# ECE445_Interrogator_Schematic.net
KiCad netlist of a schematic drawn in EAGLE
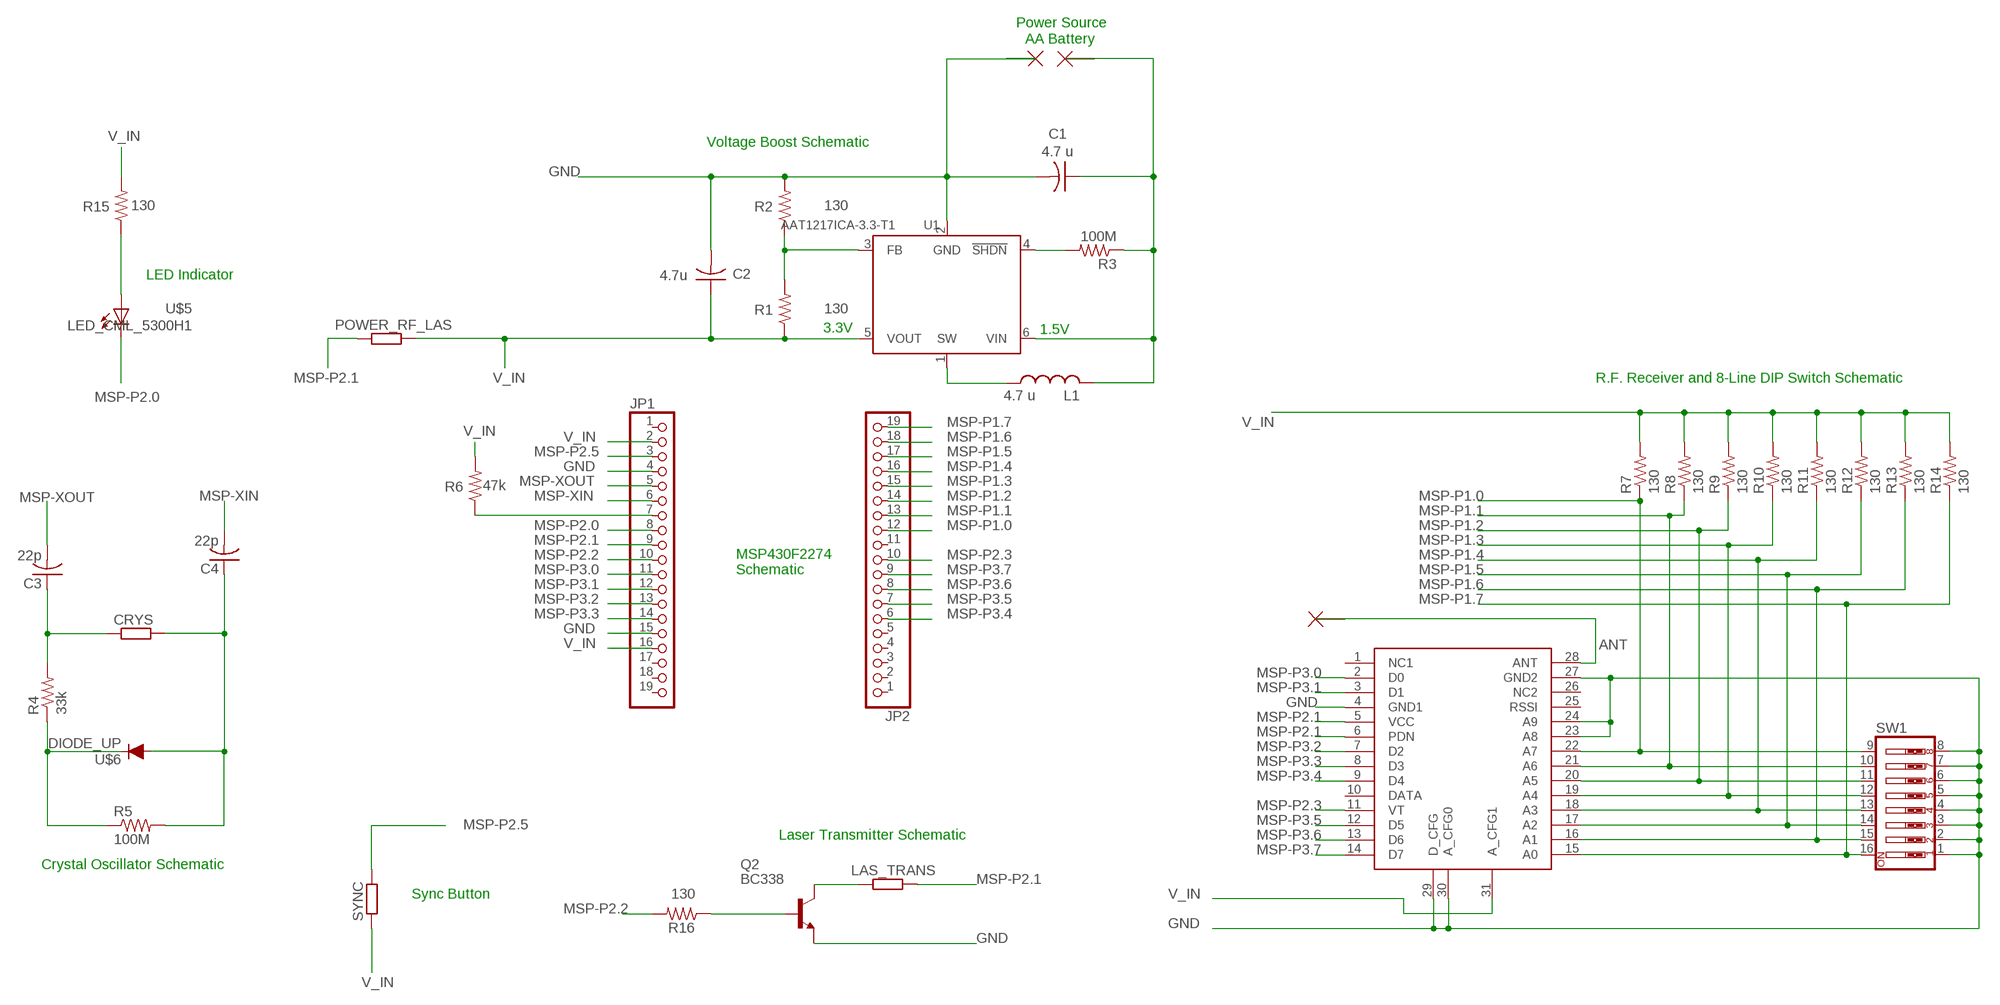
[diagram p0: schematic, sheet 1]

(export (version "E")
  (design (tool "Eeschema 10.0.6"))
  (components
    (comp (ref "C1")
      (value "4.7 u")
      (footprint "eagle-import:C025-024X044")
      (libsource (lib "eagle-import") (part "C-US025-024X044"))
    )
    (comp (ref "C2")
      (value "4.7u")
      (footprint "eagle-import:C025-024X044")
      (libsource (lib "eagle-import") (part "C-US025-024X044"))
    )
    (comp (ref "C3")
      (value "22p")
      (footprint "eagle-import:C025-024X044")
      (libsource (lib "eagle-import") (part "C-US025-024X044"))
    )
    (comp (ref "C4")
      (value "22p")
      (footprint "eagle-import:C025-024X044")
      (libsource (lib "eagle-import") (part "C-US025-024X044"))
    )
    (comp (ref "CRYS")
      (value "R-EU_0204/5")
      (footprint "eagle-import:0204_5")
      (libsource (lib "eagle-import") (part "R-EU_0204/5"))
    )
    (comp (ref "JP1")
      (value "PINHD-1X19")
      (footprint "eagle-import:1X19")
      (libsource (lib "eagle-import") (part "PINHD-1X19"))
    )
    (comp (ref "JP2")
      (value "PINHD-1X19")
      (footprint "eagle-import:1X19")
      (libsource (lib "eagle-import") (part "PINHD-1X19"))
    )
    (comp (ref "L1")
      (value "4.7 u")
      (footprint "eagle-import:0204_5")
      (libsource (lib "eagle-import") (part "L-US0204/5"))
    )
    (comp (ref "LAS_TRANS")
      (value "R-EU_0204/5")
      (footprint "eagle-import:0204_5")
      (libsource (lib "eagle-import") (part "R-EU_0204/5"))
    )
    (comp (ref "POWER_RF_LAS")
      (value "R-EU_0204/5")
      (footprint "eagle-import:0204_5")
      (libsource (lib "eagle-import") (part "R-EU_0204/5"))
    )
    (comp (ref "Q2")
      (value "BC338")
      (footprint "eagle-import:TO92-EBC")
      (libsource (lib "eagle-import") (part "BC338"))
    )
    (comp (ref "R1")
      (value "130")
      (footprint "eagle-import:0204_5")
      (libsource (lib "eagle-import") (part "R-US_0204/5"))
    )
    (comp (ref "R2")
      (value "130")
      (footprint "eagle-import:0204_5")
      (libsource (lib "eagle-import") (part "R-US_0204/5"))
    )
    (comp (ref "R3")
      (value "100M")
      (footprint "eagle-import:0204V")
      (libsource (lib "eagle-import") (part "R-US_0204/2V"))
    )
    (comp (ref "R4")
      (value "33k")
      (footprint "eagle-import:0204V")
      (libsource (lib "eagle-import") (part "R-US_0204/2V"))
    )
    (comp (ref "R5")
      (value "100M")
      (footprint "eagle-import:0204V")
      (libsource (lib "eagle-import") (part "R-US_0204/2V"))
    )
    (comp (ref "R6")
      (value "47k")
      (footprint "eagle-import:0204_5")
      (libsource (lib "eagle-import") (part "R-US_0204/5"))
    )
    (comp (ref "R7")
      (value "130")
      (footprint "eagle-import:0204_5")
      (libsource (lib "eagle-import") (part "R-US_0204/5"))
    )
    (comp (ref "R8")
      (value "130")
      (footprint "eagle-import:0204_5")
      (libsource (lib "eagle-import") (part "R-US_0204/5"))
    )
    (comp (ref "R9")
      (value "130")
      (footprint "eagle-import:0204_5")
      (libsource (lib "eagle-import") (part "R-US_0204/5"))
    )
    (comp (ref "R10")
      (value "130")
      (footprint "eagle-import:0204_5")
      (libsource (lib "eagle-import") (part "R-US_0204/5"))
    )
    (comp (ref "R11")
      (value "130")
      (footprint "eagle-import:0204_5")
      (libsource (lib "eagle-import") (part "R-US_0204/5"))
    )
    (comp (ref "R12")
      (value "130")
      (footprint "eagle-import:0204_5")
      (libsource (lib "eagle-import") (part "R-US_0204/5"))
    )
    (comp (ref "R13")
      (value "130")
      (footprint "eagle-import:0204_5")
      (libsource (lib "eagle-import") (part "R-US_0204/5"))
    )
    (comp (ref "R14")
      (value "130")
      (footprint "eagle-import:0204_5")
      (libsource (lib "eagle-import") (part "R-US_0204/5"))
    )
    (comp (ref "R15")
      (value "130")
      (footprint "eagle-import:0204_5")
      (libsource (lib "eagle-import") (part "R-US_0204/5"))
    )
    (comp (ref "R16")
      (value "130")
      (footprint "eagle-import:0204_5")
      (libsource (lib "eagle-import") (part "R-US_0204/5"))
    )
    (comp (ref "SW1")
      (value "SW_DIP-8")
      (footprint "eagle-import:EDG-08")
      (libsource (lib "eagle-import") (part "SW_DIP-8"))
    )
    (comp (ref "SYNC")
      (value "R-EU_0204/5")
      (footprint "eagle-import:0204_5")
      (libsource (lib "eagle-import") (part "R-EU_0204/5"))
    )
    (comp (ref "U$1")
      (value "KH3-RXM-LINX-315")
      (footprint "eagle-import:KH3-RXM-LINX-315")
      (libsource (lib "eagle-import") (part "KH3-RXM-LINX-315"))
    )
    (comp (ref "U$2")
      (value "NO_CONNECT")
      (footprint "eagle-import:NO_CONNECT")
      (libsource (lib "eagle-import") (part "NO_CONNECT"))
    )
    (comp (ref "U$3")
      (value "NO_CONNECT")
      (footprint "eagle-import:NO_CONNECT")
      (libsource (lib "eagle-import") (part "NO_CONNECT"))
    )
    (comp (ref "U$4")
      (value "NO_CONNECT")
      (footprint "eagle-import:NO_CONNECT")
      (libsource (lib "eagle-import") (part "NO_CONNECT"))
    )
    (comp (ref "U$5")
      (value "LED_CML_5300H1")
      (footprint "eagle-import:LED_CML_5300H1")
      (libsource (lib "eagle-import") (part "LED_CML_5300H1"))
    )
    (comp (ref "U$6")
      (value "DIODE_UP")
      (footprint "eagle-import:DIODEUP")
      (libsource (lib "eagle-import") (part "DIODE_UP"))
    )
    (comp (ref "U1")
      (value "AAT1217ICA-3.3-T1")
      (footprint "eagle-import:TSOT-23-6")
      (libsource (lib "eagle-import") (part "AAT1217ICA-3.3-T1"))
    )
  )
  (nets
    (net (code "1") (name "/ANT") (class "Default")
      (node (ref "U$1") (pin "28") (pinfunction "ANT_28") (pintype "bidirectional"))
      (node (ref "U$4") (pin "P$1") (pinfunction "NC_P$1") (pintype "bidirectional"))
    )
    (net (code "2") (name "/GND") (class "Default")
      (node (ref "C1") (pin "2") (pinfunction "2_2") (pintype "passive"))
      (node (ref "C2") (pin "2") (pinfunction "2_2") (pintype "passive"))
      (node (ref "JP1") (pin "15") (pinfunction "15_15") (pintype "passive"))
      (node (ref "JP1") (pin "4") (pinfunction "4_4") (pintype "passive"))
      (node (ref "Q2") (pin "E") (pinfunction "E_E") (pintype "passive"))
      (node (ref "R2") (pin "2") (pinfunction "2_2") (pintype "passive"))
      (node (ref "SW1") (pin "1") (pinfunction "1_1") (pintype "passive"))
      (node (ref "SW1") (pin "2") (pinfunction "2_2") (pintype "passive"))
      (node (ref "SW1") (pin "3") (pinfunction "3_3") (pintype "passive"))
      (node (ref "SW1") (pin "4") (pinfunction "4_4") (pintype "passive"))
      (node (ref "SW1") (pin "5") (pinfunction "5_5") (pintype "passive"))
      (node (ref "SW1") (pin "6") (pinfunction "6_6") (pintype "passive"))
      (node (ref "SW1") (pin "7") (pinfunction "7_7") (pintype "passive"))
      (node (ref "SW1") (pin "8") (pinfunction "8_8") (pintype "passive"))
      (node (ref "U$1") (pin "23") (pinfunction "A8_23") (pintype "bidirectional"))
      (node (ref "U$1") (pin "24") (pinfunction "A9_24") (pintype "bidirectional"))
      (node (ref "U$1") (pin "27") (pinfunction "GND2_27") (pintype "bidirectional"))
      (node (ref "U$1") (pin "29") (pinfunction "D_CFG_29") (pintype "bidirectional"))
      (node (ref "U$1") (pin "30") (pinfunction "A_CFG0_30") (pintype "bidirectional"))
      (node (ref "U$1") (pin "4") (pinfunction "GND1_4") (pintype "bidirectional"))
      (node (ref "U$2") (pin "P$1") (pinfunction "NC_P$1") (pintype "bidirectional"))
      (node (ref "U1") (pin "2") (pinfunction "GND_2") (pintype "bidirectional"))
    )
    (net (code "3") (name "/MSP-P1.0") (class "Default")
      (node (ref "JP2") (pin "12") (pinfunction "12_12") (pintype "passive"))
      (node (ref "R7") (pin "1") (pinfunction "1_1") (pintype "passive"))
      (node (ref "SW1") (pin "9") (pinfunction "9_9") (pintype "passive"))
      (node (ref "U$1") (pin "22") (pinfunction "A7_22") (pintype "bidirectional"))
    )
    (net (code "4") (name "/MSP-P1.1") (class "Default")
      (node (ref "JP2") (pin "13") (pinfunction "13_13") (pintype "passive"))
      (node (ref "R8") (pin "1") (pinfunction "1_1") (pintype "passive"))
      (node (ref "SW1") (pin "10") (pinfunction "10_10") (pintype "passive"))
      (node (ref "U$1") (pin "21") (pinfunction "A6_21") (pintype "bidirectional"))
    )
    (net (code "5") (name "/MSP-P1.2") (class "Default")
      (node (ref "JP2") (pin "14") (pinfunction "14_14") (pintype "passive"))
      (node (ref "R9") (pin "1") (pinfunction "1_1") (pintype "passive"))
      (node (ref "SW1") (pin "11") (pinfunction "11_11") (pintype "passive"))
      (node (ref "U$1") (pin "20") (pinfunction "A5_20") (pintype "bidirectional"))
    )
    (net (code "6") (name "/MSP-P1.3") (class "Default")
      (node (ref "JP2") (pin "15") (pinfunction "15_15") (pintype "passive"))
      (node (ref "R10") (pin "1") (pinfunction "1_1") (pintype "passive"))
      (node (ref "SW1") (pin "12") (pinfunction "12_12") (pintype "passive"))
      (node (ref "U$1") (pin "19") (pinfunction "A4_19") (pintype "bidirectional"))
    )
    (net (code "7") (name "/MSP-P1.4") (class "Default")
      (node (ref "JP2") (pin "16") (pinfunction "16_16") (pintype "passive"))
      (node (ref "R11") (pin "1") (pinfunction "1_1") (pintype "passive"))
      (node (ref "SW1") (pin "13") (pinfunction "13_13") (pintype "passive"))
      (node (ref "U$1") (pin "18") (pinfunction "A3_18") (pintype "bidirectional"))
    )
    (net (code "8") (name "/MSP-P1.5") (class "Default")
      (node (ref "JP2") (pin "17") (pinfunction "17_17") (pintype "passive"))
      (node (ref "R12") (pin "1") (pinfunction "1_1") (pintype "passive"))
      (node (ref "SW1") (pin "14") (pinfunction "14_14") (pintype "passive"))
      (node (ref "U$1") (pin "17") (pinfunction "A2_17") (pintype "bidirectional"))
    )
    (net (code "9") (name "/MSP-P1.6") (class "Default")
      (node (ref "JP2") (pin "18") (pinfunction "18_18") (pintype "passive"))
      (node (ref "R13") (pin "1") (pinfunction "1_1") (pintype "passive"))
      (node (ref "SW1") (pin "15") (pinfunction "15_15") (pintype "passive"))
      (node (ref "U$1") (pin "16") (pinfunction "A1_16") (pintype "bidirectional"))
    )
    (net (code "10") (name "/MSP-P1.7") (class "Default")
      (node (ref "JP2") (pin "19") (pinfunction "19_19") (pintype "passive"))
      (node (ref "R14") (pin "1") (pinfunction "1_1") (pintype "passive"))
      (node (ref "SW1") (pin "16") (pinfunction "16_16") (pintype "passive"))
      (node (ref "U$1") (pin "15") (pinfunction "A0_15") (pintype "bidirectional"))
    )
    (net (code "11") (name "/MSP-P2.0") (class "Default")
      (node (ref "JP1") (pin "8") (pinfunction "8_8") (pintype "passive"))
      (node (ref "U$5") (pin "P$2") (pinfunction "C_P$2") (pintype "passive"))
    )
    (net (code "12") (name "/MSP-P2.1") (class "Default")
      (node (ref "JP1") (pin "9") (pinfunction "9_9") (pintype "passive"))
      (node (ref "LAS_TRANS") (pin "2") (pinfunction "2_2") (pintype "passive"))
      (node (ref "POWER_RF_LAS") (pin "1") (pinfunction "1_1") (pintype "passive"))
      (node (ref "U$1") (pin "5") (pinfunction "VCC_5") (pintype "bidirectional"))
      (node (ref "U$1") (pin "6") (pinfunction "PDN_6") (pintype "bidirectional"))
    )
    (net (code "13") (name "/MSP-P2.2") (class "Default")
      (node (ref "JP1") (pin "10") (pinfunction "10_10") (pintype "passive"))
      (node (ref "R16") (pin "2") (pinfunction "2_2") (pintype "passive"))
    )
    (net (code "14") (name "/MSP-P2.3") (class "Default")
      (node (ref "JP2") (pin "10") (pinfunction "10_10") (pintype "passive"))
      (node (ref "U$1") (pin "11") (pinfunction "VT_11") (pintype "bidirectional"))
    )
    (net (code "15") (name "/MSP-P2.5") (class "Default")
      (node (ref "JP1") (pin "3") (pinfunction "3_3") (pintype "passive"))
      (node (ref "SYNC") (pin "2") (pinfunction "2_2") (pintype "passive"))
    )
    (net (code "16") (name "/MSP-P3.0") (class "Default")
      (node (ref "JP1") (pin "11") (pinfunction "11_11") (pintype "passive"))
      (node (ref "U$1") (pin "2") (pinfunction "D0_2") (pintype "bidirectional"))
    )
    (net (code "17") (name "/MSP-P3.1") (class "Default")
      (node (ref "JP1") (pin "12") (pinfunction "12_12") (pintype "passive"))
      (node (ref "U$1") (pin "3") (pinfunction "D1_3") (pintype "bidirectional"))
    )
    (net (code "18") (name "/MSP-P3.2") (class "Default")
      (node (ref "JP1") (pin "13") (pinfunction "13_13") (pintype "passive"))
      (node (ref "U$1") (pin "7") (pinfunction "D2_7") (pintype "bidirectional"))
    )
    (net (code "19") (name "/MSP-P3.3") (class "Default")
      (node (ref "JP1") (pin "14") (pinfunction "14_14") (pintype "passive"))
      (node (ref "U$1") (pin "8") (pinfunction "D3_8") (pintype "bidirectional"))
    )
    (net (code "20") (name "/MSP-P3.4") (class "Default")
      (node (ref "JP2") (pin "6") (pinfunction "6_6") (pintype "passive"))
      (node (ref "U$1") (pin "9") (pinfunction "D4_9") (pintype "bidirectional"))
    )
    (net (code "21") (name "/MSP-P3.5") (class "Default")
      (node (ref "JP2") (pin "7") (pinfunction "7_7") (pintype "passive"))
      (node (ref "U$1") (pin "12") (pinfunction "D5_12") (pintype "bidirectional"))
    )
    (net (code "22") (name "/MSP-P3.6") (class "Default")
      (node (ref "JP2") (pin "8") (pinfunction "8_8") (pintype "passive"))
      (node (ref "U$1") (pin "13") (pinfunction "D6_13") (pintype "bidirectional"))
    )
    (net (code "23") (name "/MSP-P3.7") (class "Default")
      (node (ref "JP2") (pin "9") (pinfunction "9_9") (pintype "passive"))
      (node (ref "U$1") (pin "14") (pinfunction "D7_14") (pintype "bidirectional"))
    )
    (net (code "24") (name "/MSP-XIN") (class "Default")
      (node (ref "C4") (pin "2") (pinfunction "2_2") (pintype "passive"))
      (node (ref "JP1") (pin "6") (pinfunction "6_6") (pintype "passive"))
    )
    (net (code "25") (name "/MSP-XOUT") (class "Default")
      (node (ref "C3") (pin "2") (pinfunction "2_2") (pintype "passive"))
      (node (ref "JP1") (pin "5") (pinfunction "5_5") (pintype "passive"))
    )
    (net (code "26") (name "/V_IN") (class "Default")
      (node (ref "C2") (pin "1") (pinfunction "1_1") (pintype "passive"))
      (node (ref "JP1") (pin "16") (pinfunction "16_16") (pintype "passive"))
      (node (ref "JP1") (pin "2") (pinfunction "2_2") (pintype "passive"))
      (node (ref "POWER_RF_LAS") (pin "2") (pinfunction "2_2") (pintype "passive"))
      (node (ref "R1") (pin "1") (pinfunction "1_1") (pintype "passive"))
      (node (ref "R10") (pin "2") (pinfunction "2_2") (pintype "passive"))
      (node (ref "R11") (pin "2") (pinfunction "2_2") (pintype "passive"))
      (node (ref "R12") (pin "2") (pinfunction "2_2") (pintype "passive"))
      (node (ref "R13") (pin "2") (pinfunction "2_2") (pintype "passive"))
      (node (ref "R14") (pin "2") (pinfunction "2_2") (pintype "passive"))
      (node (ref "R15") (pin "2") (pinfunction "2_2") (pintype "passive"))
      (node (ref "R6") (pin "2") (pinfunction "2_2") (pintype "passive"))
      (node (ref "R7") (pin "2") (pinfunction "2_2") (pintype "passive"))
      (node (ref "R8") (pin "2") (pinfunction "2_2") (pintype "passive"))
      (node (ref "R9") (pin "2") (pinfunction "2_2") (pintype "passive"))
      (node (ref "SYNC") (pin "1") (pinfunction "1_1") (pintype "passive"))
      (node (ref "U$1") (pin "31") (pinfunction "A_CFG1_31") (pintype "bidirectional"))
      (node (ref "U1") (pin "5") (pinfunction "VOUT_5") (pintype "bidirectional"))
    )
    (net (code "27") (name "Net-(C3-Pad1)") (class "Default")
      (node (ref "C3") (pin "1") (pinfunction "1_1") (pintype "passive"))
      (node (ref "CRYS") (pin "1") (pinfunction "1_1") (pintype "passive"))
      (node (ref "R4") (pin "2") (pinfunction "2_2") (pintype "passive"))
    )
    (net (code "28") (name "Net-(C4-Pad1)") (class "Default")
      (node (ref "C4") (pin "1") (pinfunction "1_1") (pintype "passive"))
      (node (ref "CRYS") (pin "2") (pinfunction "2_2") (pintype "passive"))
      (node (ref "R5") (pin "2") (pinfunction "2_2") (pintype "passive"))
      (node (ref "U$6") (pin "A") (pinfunction "A_A") (pintype "passive"))
    )
    (net (code "29") (name "Net-(JP1-Pad7)") (class "Default")
      (node (ref "JP1") (pin "7") (pinfunction "7_7") (pintype "passive"))
      (node (ref "R6") (pin "1") (pinfunction "1_1") (pintype "passive"))
    )
    (net (code "30") (name "Net-(LAS_TRANS-Pad1)") (class "Default")
      (node (ref "LAS_TRANS") (pin "1") (pinfunction "1_1") (pintype "passive"))
      (node (ref "Q2") (pin "C") (pinfunction "C_C") (pintype "passive"))
    )
    (net (code "31") (name "Net-(Q2-PadB)") (class "Default")
      (node (ref "Q2") (pin "B") (pinfunction "B_B") (pintype "passive"))
      (node (ref "R16") (pin "1") (pinfunction "1_1") (pintype "passive"))
    )
    (net (code "32") (name "Net-(R4-Pad1)") (class "Default")
      (node (ref "R4") (pin "1") (pinfunction "1_1") (pintype "passive"))
      (node (ref "R5") (pin "1") (pinfunction "1_1") (pintype "passive"))
      (node (ref "U$6") (pin "C") (pinfunction "C_C") (pintype "passive"))
    )
    (net (code "33") (name "Net-(U$3-NC)") (class "Default")
      (node (ref "C1") (pin "1") (pinfunction "1_1") (pintype "passive"))
      (node (ref "L1") (pin "2") (pinfunction "2_2") (pintype "passive"))
      (node (ref "R3") (pin "1") (pinfunction "1_1") (pintype "passive"))
      (node (ref "U$3") (pin "P$1") (pinfunction "NC_P$1") (pintype "bidirectional"))
      (node (ref "U1") (pin "6") (pinfunction "VIN_6") (pintype "bidirectional"))
    )
    (net (code "34") (name "Net-(U$5-A)") (class "Default")
      (node (ref "R15") (pin "1") (pinfunction "1_1") (pintype "passive"))
      (node (ref "U$5") (pin "P$1") (pinfunction "A_P$1") (pintype "passive"))
    )
    (net (code "35") (name "Net-(U1-FB)") (class "Default")
      (node (ref "R1") (pin "2") (pinfunction "2_2") (pintype "passive"))
      (node (ref "R2") (pin "1") (pinfunction "1_1") (pintype "passive"))
      (node (ref "U1") (pin "3") (pinfunction "FB_3") (pintype "bidirectional"))
    )
    (net (code "36") (name "Net-(U1-SW)") (class "Default")
      (node (ref "L1") (pin "1") (pinfunction "1_1") (pintype "passive"))
      (node (ref "U1") (pin "1") (pinfunction "SW_1") (pintype "bidirectional"))
    )
    (net (code "37") (name "Net-(U1-~{SHDN})") (class "Default")
      (node (ref "R3") (pin "2") (pinfunction "2_2") (pintype "passive"))
      (node (ref "U1") (pin "4") (pinfunction "~{SHDN}_4") (pintype "bidirectional"))
    )
    (net (code "38") (name "unconnected-(JP1-Pad1)") (class "Default")
      (node (ref "JP1") (pin "1") (pinfunction "1_1") (pintype "passive"))
    )
    (net (code "39") (name "unconnected-(JP1-Pad17)") (class "Default")
      (node (ref "JP1") (pin "17") (pinfunction "17_17") (pintype "passive"))
    )
    (net (code "40") (name "unconnected-(JP1-Pad18)") (class "Default")
      (node (ref "JP1") (pin "18") (pinfunction "18_18") (pintype "passive"))
    )
    (net (code "41") (name "unconnected-(JP1-Pad19)") (class "Default")
      (node (ref "JP1") (pin "19") (pinfunction "19_19") (pintype "passive"))
    )
    (net (code "42") (name "unconnected-(JP2-Pad1)") (class "Default")
      (node (ref "JP2") (pin "1") (pinfunction "1_1") (pintype "passive"))
    )
    (net (code "43") (name "unconnected-(JP2-Pad2)") (class "Default")
      (node (ref "JP2") (pin "2") (pinfunction "2_2") (pintype "passive"))
    )
    (net (code "44") (name "unconnected-(JP2-Pad3)") (class "Default")
      (node (ref "JP2") (pin "3") (pinfunction "3_3") (pintype "passive"))
    )
    (net (code "45") (name "unconnected-(JP2-Pad4)") (class "Default")
      (node (ref "JP2") (pin "4") (pinfunction "4_4") (pintype "passive"))
    )
    (net (code "46") (name "unconnected-(JP2-Pad5)") (class "Default")
      (node (ref "JP2") (pin "5") (pinfunction "5_5") (pintype "passive"))
    )
    (net (code "47") (name "unconnected-(JP2-Pad11)") (class "Default")
      (node (ref "JP2") (pin "11") (pinfunction "11_11") (pintype "passive"))
    )
    (net (code "48") (name "unconnected-(U$1-DATA-Pad10)") (class "Default")
      (node (ref "U$1") (pin "10") (pinfunction "DATA_10") (pintype "bidirectional"))
    )
    (net (code "49") (name "unconnected-(U$1-NC1-Pad1)") (class "Default")
      (node (ref "U$1") (pin "1") (pinfunction "NC1_1") (pintype "no_connect"))
    )
    (net (code "50") (name "unconnected-(U$1-NC2-Pad26)") (class "Default")
      (node (ref "U$1") (pin "26") (pinfunction "NC2_26") (pintype "no_connect"))
    )
    (net (code "51") (name "unconnected-(U$1-RSSI-Pad25)") (class "Default")
      (node (ref "U$1") (pin "25") (pinfunction "RSSI_25") (pintype "bidirectional"))
    )
  )
)
